# EE209_Schematic.net
KiCad netlist of a schematic drawn in Altium Designer
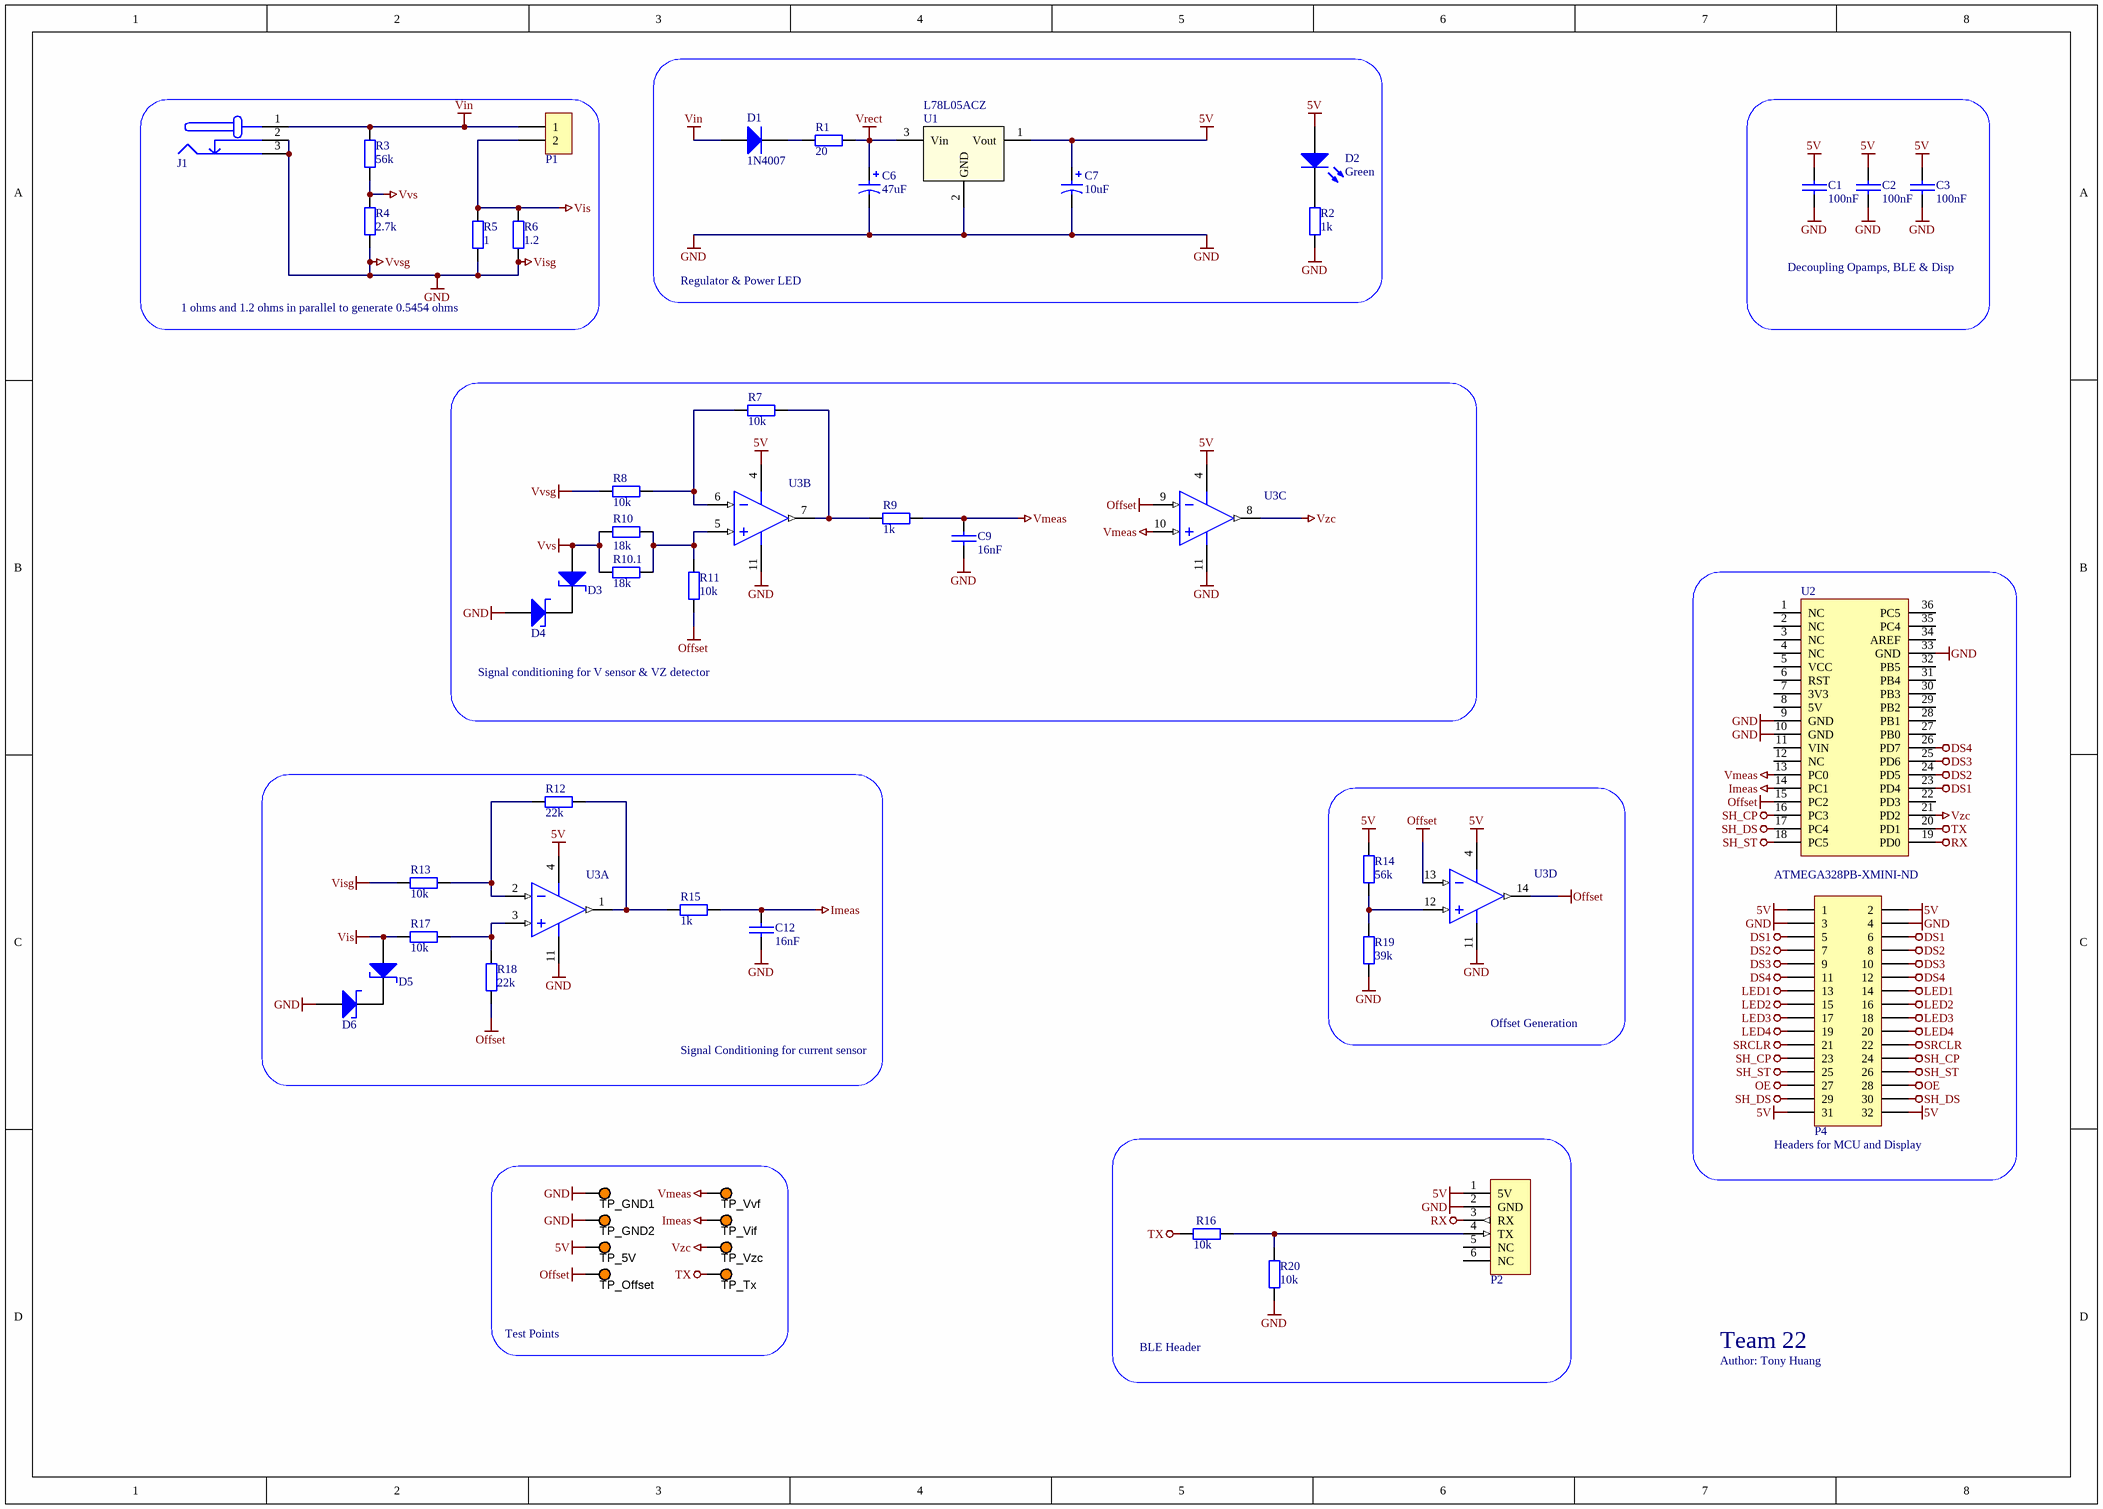
[diagram p0: EE209_Schematic.SchDoc]

(export (version "E")
  (design (tool "Eeschema 10.0.6"))
  (components
    (comp (ref "C1")
      (value "100nF")
      (footprint "CCAP-5P0")
      (description "TH ceramic capacitor with 5mm pitch")
      (libsource (lib "EE209_Library") (part "CerCap_TH_5P0"))
    )
    (comp (ref "C2")
      (value "100nF")
      (footprint "CCAP-5P0")
      (description "TH ceramic capacitor with 5mm pitch")
      (libsource (lib "EE209_Library") (part "CerCap_TH_5P0"))
    )
    (comp (ref "C3")
      (value "100nF")
      (footprint "CCAP-5P0")
      (description "TH ceramic capacitor with 5mm pitch")
      (libsource (lib "EE209_Library") (part "CerCap_TH_5P0"))
    )
    (comp (ref "C6")
      (value "47uF")
      (footprint "CAP-RAD-2.5mm Pitch")
      (description "Electrolytic capacitor with radial package, 2mm pitch and 5.2mm diameter")
      (fields (field (name "PUBLISHER") "Altium Limited"))
      (libsource (lib "EE209_Library") (part "ElecCap_TH_2P0"))
    )
    (comp (ref "C7")
      (value "10uF")
      (footprint "CAP-RAD-2.5mm Pitch")
      (description "Electrolytic capacitor with radial package, 2mm pitch and 5.2mm diameter")
      (fields (field (name "PUBLISHER") "Altium Limited"))
      (libsource (lib "EE209_Library") (part "ElecCap_TH_2P0"))
    )
    (comp (ref "C9")
      (value "16nF")
      (footprint "CCAP-5P0")
      (description "TH ceramic capacitor with 5mm pitch")
      (libsource (lib "EE209_Library") (part "CerCap_TH_5P0"))
    )
    (comp (ref "C12")
      (value "16nF")
      (footprint "CCAP-5P0")
      (description "TH ceramic capacitor with 5mm pitch")
      (libsource (lib "EE209_Library") (part "CerCap_TH_5P0"))
    )
    (comp (ref "D1")
      (value "1N4007")
      (footprint "1N4007-MFG")
      (description "1N4007 1000V standard axial diode")
      (libsource (lib "EE209_Library") (part "1N4007_TH_4AX0"))
    )
    (comp (ref "D2")
      (value "Green")
      (footprint "LED")
      (description "Typical throughole GaAs LED with 2.54mm pitch")
      (fields (field (name "MANUFACTURER") "Generic Components") (field (name "PUBLISHER") "Altium Limited"))
      (libsource (lib "EE209_Library") (part "LED_TH_2P54"))
    )
    (comp (ref "D3")
      (value "BZX79-CXVX")
      (footprint "AXIAL-Zener-0.4")
      (description "Axial zener diode BZX79 series")
      (fields
        (field (name "MANUFACTURER") "Nexperia USA Inc.")
        (field (name "MANUFACTURER PART NUMBER") "BZX79-C4V7,143")
      )
      (libsource (lib "EE209_Library") (part "Zener_TH_4AX0"))
    )
    (comp (ref "D4")
      (value "BZX79-CXVX")
      (footprint "AXIAL-Zener-0.4")
      (description "Axial zener diode BZX79 series")
      (fields
        (field (name "MANUFACTURER") "Nexperia USA Inc.")
        (field (name "MANUFACTURER PART NUMBER") "BZX79-C4V7,143")
      )
      (libsource (lib "EE209_Library") (part "Zener_TH_4AX0"))
    )
    (comp (ref "D5")
      (value "BZX79-CXVX")
      (footprint "AXIAL-Zener-0.4")
      (description "Axial zener diode BZX79 series")
      (fields
        (field (name "MANUFACTURER") "Nexperia USA Inc.")
        (field (name "MANUFACTURER PART NUMBER") "BZX79-C4V7,143")
      )
      (libsource (lib "EE209_Library") (part "Zener_TH_4AX0"))
    )
    (comp (ref "D6")
      (value "BZX79-CXVX")
      (footprint "AXIAL-Zener-0.4")
      (description "Axial zener diode BZX79 series")
      (fields
        (field (name "MANUFACTURER") "Nexperia USA Inc.")
        (field (name "MANUFACTURER PART NUMBER") "BZX79-C4V7,143")
      )
      (libsource (lib "EE209_Library") (part "Zener_TH_4AX0"))
    )
    (comp (ref "J1")
      (value "DC barrel jack")
      (footprint "AC-Socket")
      (description "DC barrel jack connection to AC source")
      (libsource (lib "EE209_Library") (part "AC_Input"))
    )
    (comp (ref "P1")
      (value "Dual Banana Plugs")
      (footprint "Dual Banana Plug")
      (description "Dual banana plugs connection to the AC load")
      (fields (field (name "PUBLISHER") "Altium Limited"))
      (libsource (lib "EE209_Library") (part "AC_Output"))
    )
    (comp (ref "P2")
      (value "BLE Module Header")
      (footprint "HM10_HDR1X6")
      (description "2.54mm pitch 6-pin header for BLE module")
      (fields (field (name "PUBLISHER") "Altium Limited"))
      (libsource (lib "EE209_Library") (part "BLEModule_TH"))
    )
    (comp (ref "P4")
      (value "Display")
      (footprint "Display")
      (description "16-Pin Header Connecting Display")
      (libsource (lib "EE209_Library") (part "Display"))
    )
    (comp (ref "R1")
      (value "20")
      (footprint "AXIAL-0.4")
      (description "Through hole resistor")
      (fields (field (name "PUBLISHER") "Altium Limited"))
      (libsource (lib "EE209_Library") (part "Res_TH_0AX4"))
    )
    (comp (ref "R2")
      (value "1k")
      (footprint "AXIAL-0.4")
      (description "Through hole resistor")
      (fields (field (name "PUBLISHER") "Altium Limited"))
      (libsource (lib "") (part "Res_TH_0AX4_3"))
    )
    (comp (ref "R3")
      (value "56k")
      (footprint "AXIAL-0.4")
      (description "Through hole resistor")
      (fields (field (name "PUBLISHER") "Altium Limited"))
      (libsource (lib "") (part "Res_TH_0AX4_1"))
    )
    (comp (ref "R4")
      (value "2.7k")
      (footprint "AXIAL-0.4")
      (description "Through hole resistor")
      (fields (field (name "PUBLISHER") "Altium Limited"))
      (libsource (lib "") (part "Res_TH_0AX4_1"))
    )
    (comp (ref "R5")
      (value "1")
      (footprint "AXIAL-0.4")
      (description "Through hole resistor")
      (fields (field (name "PUBLISHER") "Altium Limited"))
      (libsource (lib "") (part "Res_TH_0AX4_1"))
    )
    (comp (ref "R6")
      (value "1.2")
      (footprint "AXIAL-0.4")
      (description "Through hole resistor")
      (fields (field (name "PUBLISHER") "Altium Limited"))
      (libsource (lib "") (part "Res_TH_0AX4_1"))
    )
    (comp (ref "R7")
      (value "10k")
      (footprint "AXIAL-0.4")
      (description "Through hole resistor")
      (fields (field (name "PUBLISHER") "Altium Limited"))
      (libsource (lib "") (part "Res_TH_0AX4_2"))
    )
    (comp (ref "R8")
      (value "10k")
      (footprint "AXIAL-0.4")
      (description "Through hole resistor")
      (fields (field (name "PUBLISHER") "Altium Limited"))
      (libsource (lib "") (part "Res_TH_0AX4_2"))
    )
    (comp (ref "R9")
      (value "1k")
      (footprint "AXIAL-0.4")
      (description "Through hole resistor")
      (fields (field (name "PUBLISHER") "Altium Limited"))
      (libsource (lib "") (part "Res_TH_0AX4_2"))
    )
    (comp (ref "R10")
      (value "18k")
      (footprint "AXIAL-0.4")
      (description "Through hole resistor")
      (fields (field (name "PUBLISHER") "Altium Limited"))
      (libsource (lib "") (part "Res_TH_0AX4_2"))
    )
    (comp (ref "R10.1")
      (value "18k")
      (footprint "AXIAL-0.4")
      (description "Through hole resistor")
      (fields (field (name "PUBLISHER") "Altium Limited"))
      (libsource (lib "") (part "Res_TH_0AX4_2"))
    )
    (comp (ref "R11")
      (value "10k")
      (footprint "AXIAL-0.4")
      (description "Through hole resistor")
      (fields (field (name "PUBLISHER") "Altium Limited"))
      (libsource (lib "") (part "Res_TH_0AX4_1"))
    )
    (comp (ref "R12")
      (value "22k")
      (footprint "AXIAL-0.4")
      (description "Through hole resistor")
      (fields (field (name "PUBLISHER") "Altium Limited"))
      (libsource (lib "") (part "Res_TH_0AX4_2"))
    )
    (comp (ref "R13")
      (value "10k")
      (footprint "AXIAL-0.4")
      (description "Through hole resistor")
      (fields (field (name "PUBLISHER") "Altium Limited"))
      (libsource (lib "") (part "Res_TH_0AX4_2"))
    )
    (comp (ref "R14")
      (value "56k")
      (footprint "AXIAL-0.4")
      (description "Through hole resistor")
      (fields (field (name "PUBLISHER") "Altium Limited"))
      (libsource (lib "") (part "Res_TH_0AX4_1"))
    )
    (comp (ref "R15")
      (value "1k")
      (footprint "AXIAL-0.4")
      (description "Through hole resistor")
      (fields (field (name "PUBLISHER") "Altium Limited"))
      (libsource (lib "") (part "Res_TH_0AX4_2"))
    )
    (comp (ref "R16")
      (value "10k")
      (footprint "AXIAL-0.4")
      (description "Through hole resistor")
      (fields (field (name "PUBLISHER") "Altium Limited"))
      (libsource (lib "") (part "Res_TH_0AX4_2"))
    )
    (comp (ref "R17")
      (value "10k")
      (footprint "AXIAL-0.4")
      (description "Through hole resistor")
      (fields (field (name "PUBLISHER") "Altium Limited"))
      (libsource (lib "") (part "Res_TH_0AX4_2"))
    )
    (comp (ref "R18")
      (value "22k")
      (footprint "AXIAL-0.4")
      (description "Through hole resistor")
      (fields (field (name "PUBLISHER") "Altium Limited"))
      (libsource (lib "") (part "Res_TH_0AX4_1"))
    )
    (comp (ref "R19")
      (value "39k")
      (footprint "AXIAL-0.4")
      (description "Through hole resistor")
      (fields (field (name "PUBLISHER") "Altium Limited"))
      (libsource (lib "") (part "Res_TH_0AX4_1"))
    )
    (comp (ref "R20")
      (value "10k")
      (footprint "AXIAL-0.4")
      (description "Through hole resistor")
      (fields (field (name "PUBLISHER") "Altium Limited"))
      (libsource (lib "") (part "Res_TH_0AX4_1"))
    )
    (comp (ref "TP_5V")
      (value "5003")
      (footprint "TP_TH")
      (description "Test Point, Orange, 1-Pin THD, RoHS")
      (libsource (lib "EE209_Library") (part "TestPoint"))
    )
    (comp (ref "TP_GND1")
      (value "5003")
      (footprint "TP_TH")
      (description "Test Point, Orange, 1-Pin THD, RoHS")
      (libsource (lib "EE209_Library") (part "TestPoint"))
    )
    (comp (ref "TP_GND2")
      (value "5003")
      (footprint "TP_TH")
      (description "Test Point, Orange, 1-Pin THD, RoHS")
      (libsource (lib "EE209_Library") (part "TestPoint"))
    )
    (comp (ref "TP_Offset")
      (value "5003")
      (footprint "TP_TH")
      (description "Test Point, Orange, 1-Pin THD, RoHS")
      (libsource (lib "EE209_Library") (part "TestPoint"))
    )
    (comp (ref "TP_Tx")
      (value "5003")
      (footprint "TP_TH")
      (description "Test Point, Orange, 1-Pin THD, RoHS")
      (libsource (lib "EE209_Library") (part "TestPoint"))
    )
    (comp (ref "TP_Vif")
      (value "5003")
      (footprint "TP_TH")
      (description "Test Point, Orange, 1-Pin THD, RoHS")
      (libsource (lib "EE209_Library") (part "TestPoint"))
    )
    (comp (ref "TP_Vvf")
      (value "5003")
      (footprint "TP_TH")
      (description "Test Point, Orange, 1-Pin THD, RoHS")
      (libsource (lib "EE209_Library") (part "TestPoint"))
    )
    (comp (ref "TP_Vzc")
      (value "5003")
      (footprint "TP_TH")
      (description "Test Point, Orange, 1-Pin THD, RoHS")
      (libsource (lib "EE209_Library") (part "TestPoint"))
    )
    (comp (ref "U1")
      (value "L78L05ACZ")
      (footprint "TO-92")
      (description "Voltage Regulator 5V")
      (fields
        (field (name "MANUFACTURER") "ON Semiconductor")
        (field (name "MANUFACTURER PART NUMBER") "LM78L05ACZX")
      )
      (libsource (lib "EE209_Library") (part "L78L05_TH_TO92"))
    )
    (comp (ref "U2")
      (value "ATmega328PB Xplained Mini Header")
      (footprint "ATmeg328P Xplained")
      (description "Dual 18-pin headers connecting to ATmega328PB Xplained Mini")
      (fields
        (field (name "MANUFACTURER") "Microchip Technology")
        (field (name "MANUFACTURER PART NUMBER") "ATMEGA328PB-XMINI")
        (field (name "SUPPLIER PART NUMBER 1") "ATMEGA328PB-XMINI-ND")
      )
      (libsource (lib "EE209_Library") (part "ATmega328PBXplained_TH"))
    )
    (comp (ref "U3")
      (value "LM324")
      (footprint "DIP-14")
      (description "IC OPAMP GP 14DIP")
      (fields
        (field (name "MANUFACTURER") "ON Semiconductor")
        (field (name "MANUFACTURER PART NUMBER") "LM324N")
      )
      (libsource (lib "EE209_Library") (part "LM324N_TH_DIP16"))
    )
  )
  (nets
    (net (code "1") (name "5V") (class "Default")
      (node (ref "C1") (pin "1") (pinfunction "1_1") (pintype "passive"))
      (node (ref "C2") (pin "1") (pinfunction "1_1") (pintype "passive"))
      (node (ref "C3") (pin "1") (pinfunction "1_1") (pintype "passive"))
      (node (ref "C7") (pin "1") (pinfunction "1_1") (pintype "passive"))
      (node (ref "D2") (pin "1") (pinfunction "A_1") (pintype "passive"))
      (node (ref "P2") (pin "1") (pinfunction "5V_1") (pintype "passive"))
      (node (ref "P4") (pin "1") (pinfunction "1_1") (pintype "passive"))
      (node (ref "P4") (pin "2") (pinfunction "2_2") (pintype "passive"))
      (node (ref "P4") (pin "31") (pinfunction "31_31") (pintype "passive"))
      (node (ref "P4") (pin "32") (pinfunction "32_32") (pintype "passive"))
      (node (ref "R14") (pin "2") (pinfunction "2_2") (pintype "passive"))
      (node (ref "TP_5V") (pin "1") (pinfunction "1_1") (pintype "passive"))
      (node (ref "U1") (pin "1") (pinfunction "Vout_1") (pintype "passive"))
      (node (ref "U3") (pin "4") (pinfunction "VDD_4") (pintype "power_in"))
    )
    (net (code "2") (name "DS1") (class "Default")
      (node (ref "P4") (pin "5") (pinfunction "5_5") (pintype "passive"))
      (node (ref "P4") (pin "6") (pinfunction "6_6") (pintype "passive"))
      (node (ref "U2") (pin "23") (pinfunction "PD4_23") (pintype "passive"))
    )
    (net (code "3") (name "DS2") (class "Default")
      (node (ref "P4") (pin "7") (pinfunction "7_7") (pintype "passive"))
      (node (ref "P4") (pin "8") (pinfunction "8_8") (pintype "passive"))
      (node (ref "U2") (pin "24") (pinfunction "PD5_24") (pintype "passive"))
    )
    (net (code "4") (name "DS3") (class "Default")
      (node (ref "P4") (pin "10") (pinfunction "10_10") (pintype "passive"))
      (node (ref "P4") (pin "9") (pinfunction "9_9") (pintype "passive"))
      (node (ref "U2") (pin "25") (pinfunction "PD6_25") (pintype "passive"))
    )
    (net (code "5") (name "DS4") (class "Default")
      (node (ref "P4") (pin "11") (pinfunction "11_11") (pintype "passive"))
      (node (ref "P4") (pin "12") (pinfunction "12_12") (pintype "passive"))
      (node (ref "U2") (pin "26") (pinfunction "PD7_26") (pintype "passive"))
    )
    (net (code "6") (name "GND") (class "Default")
      (node (ref "C1") (pin "2") (pinfunction "2_2") (pintype "passive"))
      (node (ref "C12") (pin "2") (pinfunction "2_2") (pintype "passive"))
      (node (ref "C2") (pin "2") (pinfunction "2_2") (pintype "passive"))
      (node (ref "C3") (pin "2") (pinfunction "2_2") (pintype "passive"))
      (node (ref "C6") (pin "2") (pinfunction "2_2") (pintype "passive"))
      (node (ref "C7") (pin "2") (pinfunction "2_2") (pintype "passive"))
      (node (ref "C9") (pin "2") (pinfunction "2_2") (pintype "passive"))
      (node (ref "D4") (pin "1") (pinfunction "A_1") (pintype "passive"))
      (node (ref "D6") (pin "1") (pinfunction "A_1") (pintype "passive"))
      (node (ref "J1") (pin "2") (pinfunction "GND_ALT_2") (pintype "power_in"))
      (node (ref "J1") (pin "3") (pinfunction "GND_3") (pintype "power_in"))
      (node (ref "P2") (pin "2") (pinfunction "GND_2") (pintype "passive"))
      (node (ref "P4") (pin "3") (pinfunction "3_3") (pintype "passive"))
      (node (ref "P4") (pin "4") (pinfunction "4_4") (pintype "passive"))
      (node (ref "R13") (pin "1") (pinfunction "1_1") (pintype "passive"))
      (node (ref "R19") (pin "1") (pinfunction "1_1") (pintype "passive"))
      (node (ref "R2") (pin "2") (pinfunction "2_2") (pintype "passive"))
      (node (ref "R20") (pin "1") (pinfunction "1_1") (pintype "passive"))
      (node (ref "R4") (pin "1") (pinfunction "1_1") (pintype "passive"))
      (node (ref "R5") (pin "1") (pinfunction "1_1") (pintype "passive"))
      (node (ref "R6") (pin "1") (pinfunction "1_1") (pintype "passive"))
      (node (ref "R8") (pin "1") (pinfunction "1_1") (pintype "passive"))
      (node (ref "TP_GND1") (pin "1") (pinfunction "1_1") (pintype "passive"))
      (node (ref "TP_GND2") (pin "1") (pinfunction "1_1") (pintype "passive"))
      (node (ref "U1") (pin "2") (pinfunction "GND_2") (pintype "passive"))
      (node (ref "U2") (pin "10") (pinfunction "GND_10") (pintype "power_in"))
      (node (ref "U2") (pin "33") (pinfunction "GND_33") (pintype "passive"))
      (node (ref "U2") (pin "9") (pinfunction "GND_9") (pintype "power_in"))
      (node (ref "U3") (pin "11") (pinfunction "VSS_11") (pintype "power_in"))
    )
    (net (code "7") (name "Imeas") (class "Default")
      (node (ref "C12") (pin "1") (pinfunction "1_1") (pintype "passive"))
      (node (ref "R15") (pin "2") (pinfunction "2_2") (pintype "passive"))
      (node (ref "TP_Vif") (pin "1") (pinfunction "1_1") (pintype "passive"))
      (node (ref "U2") (pin "14") (pinfunction "PC1_14") (pintype "passive"))
    )
    (net (code "8") (name "LED1") (class "Default")
      (node (ref "P4") (pin "13") (pinfunction "13_13") (pintype "passive"))
      (node (ref "P4") (pin "14") (pinfunction "14_14") (pintype "passive"))
    )
    (net (code "9") (name "LED2") (class "Default")
      (node (ref "P4") (pin "15") (pinfunction "15_15") (pintype "passive"))
      (node (ref "P4") (pin "16") (pinfunction "16_16") (pintype "passive"))
    )
    (net (code "10") (name "LED3") (class "Default")
      (node (ref "P4") (pin "17") (pinfunction "17_17") (pintype "passive"))
      (node (ref "P4") (pin "18") (pinfunction "18_18") (pintype "passive"))
    )
    (net (code "11") (name "LED4") (class "Default")
      (node (ref "P4") (pin "19") (pinfunction "19_19") (pintype "passive"))
      (node (ref "P4") (pin "20") (pinfunction "20_20") (pintype "passive"))
    )
    (net (code "12") (name "Net-(D1-K)") (class "Default")
      (node (ref "D1") (pin "2") (pinfunction "K_2") (pintype "passive"))
      (node (ref "R1") (pin "2") (pinfunction "2_2") (pintype "passive"))
    )
    (net (code "13") (name "Net-(D2-K)") (class "Default")
      (node (ref "D2") (pin "2") (pinfunction "K_2") (pintype "passive"))
      (node (ref "R2") (pin "1") (pinfunction "1_1") (pintype "passive"))
    )
    (net (code "14") (name "Net-(D3-K)") (class "Default")
      (node (ref "D3") (pin "2") (pinfunction "K_2") (pintype "passive"))
      (node (ref "D4") (pin "2") (pinfunction "K_2") (pintype "passive"))
    )
    (net (code "15") (name "Net-(D5-K)") (class "Default")
      (node (ref "D5") (pin "2") (pinfunction "K_2") (pintype "passive"))
      (node (ref "D6") (pin "2") (pinfunction "K_2") (pintype "passive"))
    )
    (net (code "16") (name "Net-(P2-TX)") (class "Default")
      (node (ref "P2") (pin "4") (pinfunction "TX_4") (pintype "input"))
      (node (ref "R16") (pin "2") (pinfunction "2_2") (pintype "passive"))
      (node (ref "R20") (pin "2") (pinfunction "2_2") (pintype "passive"))
    )
    (net (code "17") (name "Net-(U3A-VINA+)") (class "Default")
      (node (ref "R17") (pin "2") (pinfunction "2_2") (pintype "passive"))
      (node (ref "R18") (pin "2") (pinfunction "2_2") (pintype "passive"))
      (node (ref "U3") (pin "3") (pinfunction "VINA+_3") (pintype "input"))
    )
    (net (code "18") (name "Net-(U3A-VINA-)") (class "Default")
      (node (ref "R12") (pin "1") (pinfunction "1_1") (pintype "passive"))
      (node (ref "R13") (pin "2") (pinfunction "2_2") (pintype "passive"))
      (node (ref "U3") (pin "2") (pinfunction "VINA-_2") (pintype "input"))
    )
    (net (code "19") (name "Net-(U3A-VOUTA)") (class "Default")
      (node (ref "R12") (pin "2") (pinfunction "2_2") (pintype "passive"))
      (node (ref "R15") (pin "1") (pinfunction "1_1") (pintype "passive"))
      (node (ref "U3") (pin "1") (pinfunction "VOUTA_1") (pintype "output"))
    )
    (net (code "20") (name "Net-(U3B-VINB+)") (class "Default")
      (node (ref "R10") (pin "2") (pinfunction "2_2") (pintype "passive"))
      (node (ref "R10.1") (pin "2") (pinfunction "2_2") (pintype "passive"))
      (node (ref "R11") (pin "2") (pinfunction "2_2") (pintype "passive"))
      (node (ref "U3") (pin "5") (pinfunction "VINB+_5") (pintype "input"))
    )
    (net (code "21") (name "Net-(U3B-VINB-)") (class "Default")
      (node (ref "R7") (pin "1") (pinfunction "1_1") (pintype "passive"))
      (node (ref "R8") (pin "2") (pinfunction "2_2") (pintype "passive"))
      (node (ref "U3") (pin "6") (pinfunction "VINB-_6") (pintype "input"))
    )
    (net (code "22") (name "Net-(U3B-VOUTB)") (class "Default")
      (node (ref "R7") (pin "2") (pinfunction "2_2") (pintype "passive"))
      (node (ref "R9") (pin "1") (pinfunction "1_1") (pintype "passive"))
      (node (ref "U3") (pin "7") (pinfunction "VOUTB_7") (pintype "output"))
    )
    (net (code "23") (name "Net-(U3D-VIND+)") (class "Default")
      (node (ref "R14") (pin "1") (pinfunction "1_1") (pintype "passive"))
      (node (ref "R19") (pin "2") (pinfunction "2_2") (pintype "passive"))
      (node (ref "U3") (pin "12") (pinfunction "VIND+_12") (pintype "input"))
    )
    (net (code "24") (name "OE") (class "Default")
      (node (ref "P4") (pin "27") (pinfunction "27_27") (pintype "passive"))
      (node (ref "P4") (pin "28") (pinfunction "28_28") (pintype "passive"))
    )
    (net (code "25") (name "Offset") (class "Default")
      (node (ref "R11") (pin "1") (pinfunction "1_1") (pintype "passive"))
      (node (ref "R18") (pin "1") (pinfunction "1_1") (pintype "passive"))
      (node (ref "TP_Offset") (pin "1") (pinfunction "1_1") (pintype "passive"))
      (node (ref "U2") (pin "15") (pinfunction "PC2_15") (pintype "passive"))
      (node (ref "U3") (pin "13") (pinfunction "VIND-_13") (pintype "input"))
      (node (ref "U3") (pin "14") (pinfunction "VOUTD_14") (pintype "output"))
      (node (ref "U3") (pin "9") (pinfunction "VINC-_9") (pintype "input"))
    )
    (net (code "26") (name "RX") (class "Default")
      (node (ref "P2") (pin "3") (pinfunction "RX_3") (pintype "output"))
      (node (ref "U2") (pin "19") (pinfunction "PD0_19") (pintype "passive"))
    )
    (net (code "27") (name "SH_CP") (class "Default")
      (node (ref "P4") (pin "23") (pinfunction "23_23") (pintype "passive"))
      (node (ref "P4") (pin "24") (pinfunction "24_24") (pintype "passive"))
      (node (ref "U2") (pin "16") (pinfunction "PC3_16") (pintype "passive"))
    )
    (net (code "28") (name "SH_DS") (class "Default")
      (node (ref "P4") (pin "29") (pinfunction "29_29") (pintype "passive"))
      (node (ref "P4") (pin "30") (pinfunction "30_30") (pintype "passive"))
      (node (ref "U2") (pin "17") (pinfunction "PC4_17") (pintype "passive"))
    )
    (net (code "29") (name "SH_ST") (class "Default")
      (node (ref "P4") (pin "25") (pinfunction "25_25") (pintype "passive"))
      (node (ref "P4") (pin "26") (pinfunction "26_26") (pintype "passive"))
      (node (ref "U2") (pin "18") (pinfunction "PC5_18") (pintype "passive"))
    )
    (net (code "30") (name "SRCLR") (class "Default")
      (node (ref "P4") (pin "21") (pinfunction "21_21") (pintype "passive"))
      (node (ref "P4") (pin "22") (pinfunction "22_22") (pintype "passive"))
    )
    (net (code "31") (name "TX") (class "Default")
      (node (ref "R16") (pin "1") (pinfunction "1_1") (pintype "passive"))
      (node (ref "TP_Tx") (pin "1") (pinfunction "1_1") (pintype "passive"))
      (node (ref "U2") (pin "20") (pinfunction "PD1_20") (pintype "passive"))
    )
    (net (code "32") (name "Vin") (class "Default")
      (node (ref "D1") (pin "1") (pinfunction "A_1") (pintype "passive"))
      (node (ref "J1") (pin "1") (pinfunction "VCC_1") (pintype "power_in"))
      (node (ref "P1") (pin "1") (pinfunction "1_1") (pintype "passive"))
      (node (ref "R3") (pin "2") (pinfunction "2_2") (pintype "passive"))
    )
    (net (code "33") (name "Vis") (class "Default")
      (node (ref "D5") (pin "1") (pinfunction "A_1") (pintype "passive"))
      (node (ref "P1") (pin "2") (pinfunction "2_2") (pintype "passive"))
      (node (ref "R17") (pin "1") (pinfunction "1_1") (pintype "passive"))
      (node (ref "R5") (pin "2") (pinfunction "2_2") (pintype "passive"))
      (node (ref "R6") (pin "2") (pinfunction "2_2") (pintype "passive"))
    )
    (net (code "34") (name "Vmeas") (class "Default")
      (node (ref "C9") (pin "1") (pinfunction "1_1") (pintype "passive"))
      (node (ref "R9") (pin "2") (pinfunction "2_2") (pintype "passive"))
      (node (ref "TP_Vvf") (pin "1") (pinfunction "1_1") (pintype "passive"))
      (node (ref "U2") (pin "13") (pinfunction "PC0_13") (pintype "passive"))
      (node (ref "U3") (pin "10") (pinfunction "VINC+_10") (pintype "input"))
    )
    (net (code "35") (name "Vrect") (class "Default")
      (node (ref "C6") (pin "1") (pinfunction "1_1") (pintype "passive"))
      (node (ref "R1") (pin "1") (pinfunction "1_1") (pintype "passive"))
      (node (ref "U1") (pin "3") (pinfunction "Vin_3") (pintype "passive"))
    )
    (net (code "36") (name "Vvs") (class "Default")
      (node (ref "D3") (pin "1") (pinfunction "A_1") (pintype "passive"))
      (node (ref "R10") (pin "1") (pinfunction "1_1") (pintype "passive"))
      (node (ref "R10.1") (pin "1") (pinfunction "1_1") (pintype "passive"))
      (node (ref "R3") (pin "1") (pinfunction "1_1") (pintype "passive"))
      (node (ref "R4") (pin "2") (pinfunction "2_2") (pintype "passive"))
    )
    (net (code "37") (name "Vzc") (class "Default")
      (node (ref "TP_Vzc") (pin "1") (pinfunction "1_1") (pintype "passive"))
      (node (ref "U2") (pin "21") (pinfunction "PD2_21") (pintype "passive"))
      (node (ref "U3") (pin "8") (pinfunction "VOUTC_8") (pintype "output"))
    )
    (net (code "38") (name "unconnected-(P2-NC-Pad5)") (class "Default")
      (node (ref "P2") (pin "5") (pinfunction "NC_5") (pintype "passive"))
    )
    (net (code "39") (name "unconnected-(P2-NC-Pad6)") (class "Default")
      (node (ref "P2") (pin "6") (pinfunction "NC_6") (pintype "passive"))
    )
    (net (code "40") (name "unconnected-(U2-3V3-Pad7)") (class "Default")
      (node (ref "U2") (pin "7") (pinfunction "3V3_7") (pintype "passive"))
    )
    (net (code "41") (name "unconnected-(U2-5V-Pad8)") (class "Default")
      (node (ref "U2") (pin "8") (pinfunction "5V_8") (pintype "power_in"))
    )
    (net (code "42") (name "unconnected-(U2-AREF-Pad34)") (class "Default")
      (node (ref "U2") (pin "34") (pinfunction "AREF_34") (pintype "passive"))
    )
    (net (code "43") (name "unconnected-(U2-NC-Pad1)") (class "Default")
      (node (ref "U2") (pin "1") (pinfunction "NC_1") (pintype "passive"))
    )
    (net (code "44") (name "unconnected-(U2-NC-Pad2)") (class "Default")
      (node (ref "U2") (pin "2") (pinfunction "NC_2") (pintype "passive"))
    )
    (net (code "45") (name "unconnected-(U2-NC-Pad3)") (class "Default")
      (node (ref "U2") (pin "3") (pinfunction "NC_3") (pintype "passive"))
    )
    (net (code "46") (name "unconnected-(U2-NC-Pad4)") (class "Default")
      (node (ref "U2") (pin "4") (pinfunction "NC_4") (pintype "passive"))
    )
    (net (code "47") (name "unconnected-(U2-NC-Pad12)") (class "Default")
      (node (ref "U2") (pin "12") (pinfunction "NC_12") (pintype "passive"))
    )
    (net (code "48") (name "unconnected-(U2-PB0-Pad27)") (class "Default")
      (node (ref "U2") (pin "27") (pinfunction "PB0_27") (pintype "passive"))
    )
    (net (code "49") (name "unconnected-(U2-PB1-Pad28)") (class "Default")
      (node (ref "U2") (pin "28") (pinfunction "PB1_28") (pintype "passive"))
    )
    (net (code "50") (name "unconnected-(U2-PB2-Pad29)") (class "Default")
      (node (ref "U2") (pin "29") (pinfunction "PB2_29") (pintype "passive"))
    )
    (net (code "51") (name "unconnected-(U2-PB3-Pad30)") (class "Default")
      (node (ref "U2") (pin "30") (pinfunction "PB3_30") (pintype "passive"))
    )
    (net (code "52") (name "unconnected-(U2-PB4-Pad31)") (class "Default")
      (node (ref "U2") (pin "31") (pinfunction "PB4_31") (pintype "passive"))
    )
    (net (code "53") (name "unconnected-(U2-PB5-Pad32)") (class "Default")
      (node (ref "U2") (pin "32") (pinfunction "PB5_32") (pintype "passive"))
    )
    (net (code "54") (name "unconnected-(U2-PC4-Pad35)") (class "Default")
      (node (ref "U2") (pin "35") (pinfunction "PC4_35") (pintype "passive"))
    )
    (net (code "55") (name "unconnected-(U2-PC5-Pad36)") (class "Default")
      (node (ref "U2") (pin "36") (pinfunction "PC5_36") (pintype "passive"))
    )
    (net (code "56") (name "unconnected-(U2-PD3-Pad22)") (class "Default")
      (node (ref "U2") (pin "22") (pinfunction "PD3_22") (pintype "passive"))
    )
    (net (code "57") (name "unconnected-(U2-RST-Pad6)") (class "Default")
      (node (ref "U2") (pin "6") (pinfunction "RST_6") (pintype "passive"))
    )
    (net (code "58") (name "unconnected-(U2-VCC-Pad5)") (class "Default")
      (node (ref "U2") (pin "5") (pinfunction "VCC_5") (pintype "power_in"))
    )
    (net (code "59") (name "unconnected-(U2-VIN-Pad11)") (class "Default")
      (node (ref "U2") (pin "11") (pinfunction "VIN_11") (pintype "power_in"))
    )
  )
)
